# led_arrays.net
KiCad netlist of a schematic drawn in EAGLE
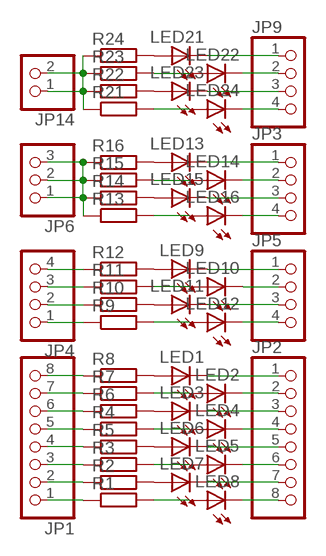
[diagram p0: schematic, sheet 1]

(export (version "E")
  (design (tool "Eeschema 10.0.6"))
  (components
    (comp (ref "JP1")
      (value "PINHD-1X8")
      (footprint "eagle-import:1X08")
      (libsource (lib "eagle-import") (part "PINHD-1X8"))
    )
    (comp (ref "JP2")
      (value "PINHD-1X8")
      (footprint "eagle-import:1X08")
      (libsource (lib "eagle-import") (part "PINHD-1X8"))
    )
    (comp (ref "JP3")
      (value "PINHD-1X4")
      (footprint "eagle-import:1X04")
      (libsource (lib "eagle-import") (part "PINHD-1X4"))
    )
    (comp (ref "JP4")
      (value "PINHD-1X4")
      (footprint "eagle-import:1X04")
      (libsource (lib "eagle-import") (part "PINHD-1X4"))
    )
    (comp (ref "JP5")
      (value "PINHD-1X4")
      (footprint "eagle-import:1X04")
      (libsource (lib "eagle-import") (part "PINHD-1X4"))
    )
    (comp (ref "JP6")
      (value "PINHD-1X3")
      (footprint "eagle-import:1X03")
      (libsource (lib "eagle-import") (part "PINHD-1X3"))
    )
    (comp (ref "JP9")
      (value "PINHD-1X4")
      (footprint "eagle-import:1X04")
      (libsource (lib "eagle-import") (part "PINHD-1X4"))
    )
    (comp (ref "JP14")
      (value "PINHD-1X2")
      (footprint "eagle-import:1X02")
      (libsource (lib "eagle-import") (part "PINHD-1X2"))
    )
    (comp (ref "LED1")
      (value "LEDSML0805")
      (footprint "eagle-import:SML0805")
      (libsource (lib "eagle-import") (part "LEDSML0805"))
    )
    (comp (ref "LED2")
      (value "LEDSML0805")
      (footprint "eagle-import:SML0805")
      (libsource (lib "eagle-import") (part "LEDSML0805"))
    )
    (comp (ref "LED3")
      (value "LEDSML0805")
      (footprint "eagle-import:SML0805")
      (libsource (lib "eagle-import") (part "LEDSML0805"))
    )
    (comp (ref "LED4")
      (value "LEDSML0805")
      (footprint "eagle-import:SML0805")
      (libsource (lib "eagle-import") (part "LEDSML0805"))
    )
    (comp (ref "LED5")
      (value "LEDSML0805")
      (footprint "eagle-import:SML0805")
      (libsource (lib "eagle-import") (part "LEDSML0805"))
    )
    (comp (ref "LED6")
      (value "LEDSML0805")
      (footprint "eagle-import:SML0805")
      (libsource (lib "eagle-import") (part "LEDSML0805"))
    )
    (comp (ref "LED7")
      (value "LEDSML0805")
      (footprint "eagle-import:SML0805")
      (libsource (lib "eagle-import") (part "LEDSML0805"))
    )
    (comp (ref "LED8")
      (value "LEDSML0805")
      (footprint "eagle-import:SML0805")
      (libsource (lib "eagle-import") (part "LEDSML0805"))
    )
    (comp (ref "LED9")
      (value "LEDSML0805")
      (footprint "eagle-import:SML0805")
      (libsource (lib "eagle-import") (part "LEDSML0805"))
    )
    (comp (ref "LED10")
      (value "LEDSML0805")
      (footprint "eagle-import:SML0805")
      (libsource (lib "eagle-import") (part "LEDSML0805"))
    )
    (comp (ref "LED11")
      (value "LEDSML0805")
      (footprint "eagle-import:SML0805")
      (libsource (lib "eagle-import") (part "LEDSML0805"))
    )
    (comp (ref "LED12")
      (value "LEDSML0805")
      (footprint "eagle-import:SML0805")
      (libsource (lib "eagle-import") (part "LEDSML0805"))
    )
    (comp (ref "LED13")
      (value "LEDSML0805")
      (footprint "eagle-import:SML0805")
      (libsource (lib "eagle-import") (part "LEDSML0805"))
    )
    (comp (ref "LED14")
      (value "LEDSML0805")
      (footprint "eagle-import:SML0805")
      (libsource (lib "eagle-import") (part "LEDSML0805"))
    )
    (comp (ref "LED15")
      (value "LEDSML0805")
      (footprint "eagle-import:SML0805")
      (libsource (lib "eagle-import") (part "LEDSML0805"))
    )
    (comp (ref "LED16")
      (value "LEDSML0805")
      (footprint "eagle-import:SML0805")
      (libsource (lib "eagle-import") (part "LEDSML0805"))
    )
    (comp (ref "LED21")
      (value "LEDSML0805")
      (footprint "eagle-import:SML0805")
      (libsource (lib "eagle-import") (part "LEDSML0805"))
    )
    (comp (ref "LED22")
      (value "LEDSML0805")
      (footprint "eagle-import:SML0805")
      (libsource (lib "eagle-import") (part "LEDSML0805"))
    )
    (comp (ref "LED23")
      (value "LEDSML0805")
      (footprint "eagle-import:SML0805")
      (libsource (lib "eagle-import") (part "LEDSML0805"))
    )
    (comp (ref "LED24")
      (value "LEDSML0805")
      (footprint "eagle-import:SML0805")
      (libsource (lib "eagle-import") (part "LEDSML0805"))
    )
    (comp (ref "R1")
      (value "R-EU_M0805")
      (footprint "eagle-import:M0805")
      (libsource (lib "eagle-import") (part "R-EU_M0805"))
    )
    (comp (ref "R2")
      (value "R-EU_M0805")
      (footprint "eagle-import:M0805")
      (libsource (lib "eagle-import") (part "R-EU_M0805"))
    )
    (comp (ref "R3")
      (value "R-EU_M0805")
      (footprint "eagle-import:M0805")
      (libsource (lib "eagle-import") (part "R-EU_M0805"))
    )
    (comp (ref "R4")
      (value "R-EU_M0805")
      (footprint "eagle-import:M0805")
      (libsource (lib "eagle-import") (part "R-EU_M0805"))
    )
    (comp (ref "R5")
      (value "R-EU_M0805")
      (footprint "eagle-import:M0805")
      (libsource (lib "eagle-import") (part "R-EU_M0805"))
    )
    (comp (ref "R6")
      (value "R-EU_M0805")
      (footprint "eagle-import:M0805")
      (libsource (lib "eagle-import") (part "R-EU_M0805"))
    )
    (comp (ref "R7")
      (value "R-EU_M0805")
      (footprint "eagle-import:M0805")
      (libsource (lib "eagle-import") (part "R-EU_M0805"))
    )
    (comp (ref "R8")
      (value "R-EU_M0805")
      (footprint "eagle-import:M0805")
      (libsource (lib "eagle-import") (part "R-EU_M0805"))
    )
    (comp (ref "R9")
      (value "R-EU_M0805")
      (footprint "eagle-import:M0805")
      (libsource (lib "eagle-import") (part "R-EU_M0805"))
    )
    (comp (ref "R10")
      (value "R-EU_M0805")
      (footprint "eagle-import:M0805")
      (libsource (lib "eagle-import") (part "R-EU_M0805"))
    )
    (comp (ref "R11")
      (value "R-EU_M0805")
      (footprint "eagle-import:M0805")
      (libsource (lib "eagle-import") (part "R-EU_M0805"))
    )
    (comp (ref "R12")
      (value "R-EU_M0805")
      (footprint "eagle-import:M0805")
      (libsource (lib "eagle-import") (part "R-EU_M0805"))
    )
    (comp (ref "R13")
      (value "R-EU_M0805")
      (footprint "eagle-import:M0805")
      (libsource (lib "eagle-import") (part "R-EU_M0805"))
    )
    (comp (ref "R14")
      (value "R-EU_M0805")
      (footprint "eagle-import:M0805")
      (libsource (lib "eagle-import") (part "R-EU_M0805"))
    )
    (comp (ref "R15")
      (value "R-EU_M0805")
      (footprint "eagle-import:M0805")
      (libsource (lib "eagle-import") (part "R-EU_M0805"))
    )
    (comp (ref "R16")
      (value "R-EU_M0805")
      (footprint "eagle-import:M0805")
      (libsource (lib "eagle-import") (part "R-EU_M0805"))
    )
    (comp (ref "R21")
      (value "R-EU_M0805")
      (footprint "eagle-import:M0805")
      (libsource (lib "eagle-import") (part "R-EU_M0805"))
    )
    (comp (ref "R22")
      (value "R-EU_M0805")
      (footprint "eagle-import:M0805")
      (libsource (lib "eagle-import") (part "R-EU_M0805"))
    )
    (comp (ref "R23")
      (value "R-EU_M0805")
      (footprint "eagle-import:M0805")
      (libsource (lib "eagle-import") (part "R-EU_M0805"))
    )
    (comp (ref "R24")
      (value "R-EU_M0805")
      (footprint "eagle-import:M0805")
      (libsource (lib "eagle-import") (part "R-EU_M0805"))
    )
  )
  (nets
    (net (code "1") (name "Net-(JP1-Pad1)") (class "Default")
      (node (ref "JP1") (pin "1") (pinfunction "1_1") (pintype "passive"))
      (node (ref "R1") (pin "1") (pinfunction "1_1") (pintype "passive"))
    )
    (net (code "2") (name "Net-(JP1-Pad2)") (class "Default")
      (node (ref "JP1") (pin "2") (pinfunction "2_2") (pintype "passive"))
      (node (ref "R2") (pin "1") (pinfunction "1_1") (pintype "passive"))
    )
    (net (code "3") (name "Net-(JP1-Pad3)") (class "Default")
      (node (ref "JP1") (pin "3") (pinfunction "3_3") (pintype "passive"))
      (node (ref "R3") (pin "1") (pinfunction "1_1") (pintype "passive"))
    )
    (net (code "4") (name "Net-(JP1-Pad4)") (class "Default")
      (node (ref "JP1") (pin "4") (pinfunction "4_4") (pintype "passive"))
      (node (ref "R5") (pin "1") (pinfunction "1_1") (pintype "passive"))
    )
    (net (code "5") (name "Net-(JP1-Pad5)") (class "Default")
      (node (ref "JP1") (pin "5") (pinfunction "5_5") (pintype "passive"))
      (node (ref "R4") (pin "1") (pinfunction "1_1") (pintype "passive"))
    )
    (net (code "6") (name "Net-(JP1-Pad6)") (class "Default")
      (node (ref "JP1") (pin "6") (pinfunction "6_6") (pintype "passive"))
      (node (ref "R6") (pin "1") (pinfunction "1_1") (pintype "passive"))
    )
    (net (code "7") (name "Net-(JP1-Pad7)") (class "Default")
      (node (ref "JP1") (pin "7") (pinfunction "7_7") (pintype "passive"))
      (node (ref "R7") (pin "1") (pinfunction "1_1") (pintype "passive"))
    )
    (net (code "8") (name "Net-(JP1-Pad8)") (class "Default")
      (node (ref "JP1") (pin "8") (pinfunction "8_8") (pintype "passive"))
      (node (ref "R8") (pin "1") (pinfunction "1_1") (pintype "passive"))
    )
    (net (code "9") (name "Net-(JP2-Pad1)") (class "Default")
      (node (ref "JP2") (pin "1") (pinfunction "1_1") (pintype "passive"))
      (node (ref "LED1") (pin "C") (pinfunction "C_C") (pintype "passive"))
    )
    (net (code "10") (name "Net-(JP2-Pad2)") (class "Default")
      (node (ref "JP2") (pin "2") (pinfunction "2_2") (pintype "passive"))
      (node (ref "LED2") (pin "C") (pinfunction "C_C") (pintype "passive"))
    )
    (net (code "11") (name "Net-(JP2-Pad3)") (class "Default")
      (node (ref "JP2") (pin "3") (pinfunction "3_3") (pintype "passive"))
      (node (ref "LED3") (pin "C") (pinfunction "C_C") (pintype "passive"))
    )
    (net (code "12") (name "Net-(JP2-Pad4)") (class "Default")
      (node (ref "JP2") (pin "4") (pinfunction "4_4") (pintype "passive"))
      (node (ref "LED4") (pin "C") (pinfunction "C_C") (pintype "passive"))
    )
    (net (code "13") (name "Net-(JP2-Pad5)") (class "Default")
      (node (ref "JP2") (pin "5") (pinfunction "5_5") (pintype "passive"))
      (node (ref "LED6") (pin "C") (pinfunction "C_C") (pintype "passive"))
    )
    (net (code "14") (name "Net-(JP2-Pad6)") (class "Default")
      (node (ref "JP2") (pin "6") (pinfunction "6_6") (pintype "passive"))
      (node (ref "LED5") (pin "C") (pinfunction "C_C") (pintype "passive"))
    )
    (net (code "15") (name "Net-(JP2-Pad7)") (class "Default")
      (node (ref "JP2") (pin "7") (pinfunction "7_7") (pintype "passive"))
      (node (ref "LED7") (pin "C") (pinfunction "C_C") (pintype "passive"))
    )
    (net (code "16") (name "Net-(JP2-Pad8)") (class "Default")
      (node (ref "JP2") (pin "8") (pinfunction "8_8") (pintype "passive"))
      (node (ref "LED8") (pin "C") (pinfunction "C_C") (pintype "passive"))
    )
    (net (code "17") (name "Net-(JP3-Pad1)") (class "Default")
      (node (ref "JP3") (pin "1") (pinfunction "1_1") (pintype "passive"))
      (node (ref "LED13") (pin "C") (pinfunction "C_C") (pintype "passive"))
    )
    (net (code "18") (name "Net-(JP3-Pad2)") (class "Default")
      (node (ref "JP3") (pin "2") (pinfunction "2_2") (pintype "passive"))
      (node (ref "LED14") (pin "C") (pinfunction "C_C") (pintype "passive"))
    )
    (net (code "19") (name "Net-(JP3-Pad3)") (class "Default")
      (node (ref "JP3") (pin "3") (pinfunction "3_3") (pintype "passive"))
      (node (ref "LED15") (pin "C") (pinfunction "C_C") (pintype "passive"))
    )
    (net (code "20") (name "Net-(JP3-Pad4)") (class "Default")
      (node (ref "JP3") (pin "4") (pinfunction "4_4") (pintype "passive"))
      (node (ref "LED16") (pin "C") (pinfunction "C_C") (pintype "passive"))
    )
    (net (code "21") (name "Net-(JP4-Pad1)") (class "Default")
      (node (ref "JP4") (pin "1") (pinfunction "1_1") (pintype "passive"))
      (node (ref "R9") (pin "1") (pinfunction "1_1") (pintype "passive"))
    )
    (net (code "22") (name "Net-(JP4-Pad2)") (class "Default")
      (node (ref "JP4") (pin "2") (pinfunction "2_2") (pintype "passive"))
      (node (ref "R10") (pin "1") (pinfunction "1_1") (pintype "passive"))
    )
    (net (code "23") (name "Net-(JP4-Pad3)") (class "Default")
      (node (ref "JP4") (pin "3") (pinfunction "3_3") (pintype "passive"))
      (node (ref "R11") (pin "1") (pinfunction "1_1") (pintype "passive"))
    )
    (net (code "24") (name "Net-(JP4-Pad4)") (class "Default")
      (node (ref "JP4") (pin "4") (pinfunction "4_4") (pintype "passive"))
      (node (ref "R12") (pin "1") (pinfunction "1_1") (pintype "passive"))
    )
    (net (code "25") (name "Net-(JP5-Pad1)") (class "Default")
      (node (ref "JP5") (pin "1") (pinfunction "1_1") (pintype "passive"))
      (node (ref "LED9") (pin "C") (pinfunction "C_C") (pintype "passive"))
    )
    (net (code "26") (name "Net-(JP5-Pad2)") (class "Default")
      (node (ref "JP5") (pin "2") (pinfunction "2_2") (pintype "passive"))
      (node (ref "LED10") (pin "C") (pinfunction "C_C") (pintype "passive"))
    )
    (net (code "27") (name "Net-(JP5-Pad3)") (class "Default")
      (node (ref "JP5") (pin "3") (pinfunction "3_3") (pintype "passive"))
      (node (ref "LED11") (pin "C") (pinfunction "C_C") (pintype "passive"))
    )
    (net (code "28") (name "Net-(JP5-Pad4)") (class "Default")
      (node (ref "JP5") (pin "4") (pinfunction "4_4") (pintype "passive"))
      (node (ref "LED12") (pin "C") (pinfunction "C_C") (pintype "passive"))
    )
    (net (code "29") (name "Net-(JP6-Pad1)") (class "Default")
      (node (ref "JP6") (pin "1") (pinfunction "1_1") (pintype "passive"))
      (node (ref "JP6") (pin "2") (pinfunction "2_2") (pintype "passive"))
      (node (ref "JP6") (pin "3") (pinfunction "3_3") (pintype "passive"))
      (node (ref "R13") (pin "1") (pinfunction "1_1") (pintype "passive"))
      (node (ref "R14") (pin "1") (pinfunction "1_1") (pintype "passive"))
      (node (ref "R15") (pin "1") (pinfunction "1_1") (pintype "passive"))
      (node (ref "R16") (pin "1") (pinfunction "1_1") (pintype "passive"))
    )
    (net (code "30") (name "Net-(JP9-Pad1)") (class "Default")
      (node (ref "JP9") (pin "1") (pinfunction "1_1") (pintype "passive"))
      (node (ref "LED21") (pin "C") (pinfunction "C_C") (pintype "passive"))
    )
    (net (code "31") (name "Net-(JP9-Pad2)") (class "Default")
      (node (ref "JP9") (pin "2") (pinfunction "2_2") (pintype "passive"))
      (node (ref "LED22") (pin "C") (pinfunction "C_C") (pintype "passive"))
    )
    (net (code "32") (name "Net-(JP9-Pad3)") (class "Default")
      (node (ref "JP9") (pin "3") (pinfunction "3_3") (pintype "passive"))
      (node (ref "LED23") (pin "C") (pinfunction "C_C") (pintype "passive"))
    )
    (net (code "33") (name "Net-(JP9-Pad4)") (class "Default")
      (node (ref "JP9") (pin "4") (pinfunction "4_4") (pintype "passive"))
      (node (ref "LED24") (pin "C") (pinfunction "C_C") (pintype "passive"))
    )
    (net (code "34") (name "Net-(JP14-Pad1)") (class "Default")
      (node (ref "JP14") (pin "1") (pinfunction "1_1") (pintype "passive"))
      (node (ref "JP14") (pin "2") (pinfunction "2_2") (pintype "passive"))
      (node (ref "R21") (pin "1") (pinfunction "1_1") (pintype "passive"))
      (node (ref "R22") (pin "1") (pinfunction "1_1") (pintype "passive"))
      (node (ref "R23") (pin "1") (pinfunction "1_1") (pintype "passive"))
      (node (ref "R24") (pin "1") (pinfunction "1_1") (pintype "passive"))
    )
    (net (code "35") (name "Net-(LED1-PadA)") (class "Default")
      (node (ref "LED1") (pin "A") (pinfunction "A_A") (pintype "passive"))
      (node (ref "R8") (pin "2") (pinfunction "2_2") (pintype "passive"))
    )
    (net (code "36") (name "Net-(LED2-PadA)") (class "Default")
      (node (ref "LED2") (pin "A") (pinfunction "A_A") (pintype "passive"))
      (node (ref "R7") (pin "2") (pinfunction "2_2") (pintype "passive"))
    )
    (net (code "37") (name "Net-(LED3-PadA)") (class "Default")
      (node (ref "LED3") (pin "A") (pinfunction "A_A") (pintype "passive"))
      (node (ref "R6") (pin "2") (pinfunction "2_2") (pintype "passive"))
    )
    (net (code "38") (name "Net-(LED4-PadA)") (class "Default")
      (node (ref "LED4") (pin "A") (pinfunction "A_A") (pintype "passive"))
      (node (ref "R4") (pin "2") (pinfunction "2_2") (pintype "passive"))
    )
    (net (code "39") (name "Net-(LED5-PadA)") (class "Default")
      (node (ref "LED5") (pin "A") (pinfunction "A_A") (pintype "passive"))
      (node (ref "R3") (pin "2") (pinfunction "2_2") (pintype "passive"))
    )
    (net (code "40") (name "Net-(LED6-PadA)") (class "Default")
      (node (ref "LED6") (pin "A") (pinfunction "A_A") (pintype "passive"))
      (node (ref "R5") (pin "2") (pinfunction "2_2") (pintype "passive"))
    )
    (net (code "41") (name "Net-(LED7-PadA)") (class "Default")
      (node (ref "LED7") (pin "A") (pinfunction "A_A") (pintype "passive"))
      (node (ref "R2") (pin "2") (pinfunction "2_2") (pintype "passive"))
    )
    (net (code "42") (name "Net-(LED8-PadA)") (class "Default")
      (node (ref "LED8") (pin "A") (pinfunction "A_A") (pintype "passive"))
      (node (ref "R1") (pin "2") (pinfunction "2_2") (pintype "passive"))
    )
    (net (code "43") (name "Net-(LED9-PadA)") (class "Default")
      (node (ref "LED9") (pin "A") (pinfunction "A_A") (pintype "passive"))
      (node (ref "R12") (pin "2") (pinfunction "2_2") (pintype "passive"))
    )
    (net (code "44") (name "Net-(LED10-PadA)") (class "Default")
      (node (ref "LED10") (pin "A") (pinfunction "A_A") (pintype "passive"))
      (node (ref "R11") (pin "2") (pinfunction "2_2") (pintype "passive"))
    )
    (net (code "45") (name "Net-(LED11-PadA)") (class "Default")
      (node (ref "LED11") (pin "A") (pinfunction "A_A") (pintype "passive"))
      (node (ref "R10") (pin "2") (pinfunction "2_2") (pintype "passive"))
    )
    (net (code "46") (name "Net-(LED12-PadA)") (class "Default")
      (node (ref "LED12") (pin "A") (pinfunction "A_A") (pintype "passive"))
      (node (ref "R9") (pin "2") (pinfunction "2_2") (pintype "passive"))
    )
    (net (code "47") (name "Net-(LED13-PadA)") (class "Default")
      (node (ref "LED13") (pin "A") (pinfunction "A_A") (pintype "passive"))
      (node (ref "R16") (pin "2") (pinfunction "2_2") (pintype "passive"))
    )
    (net (code "48") (name "Net-(LED14-PadA)") (class "Default")
      (node (ref "LED14") (pin "A") (pinfunction "A_A") (pintype "passive"))
      (node (ref "R15") (pin "2") (pinfunction "2_2") (pintype "passive"))
    )
    (net (code "49") (name "Net-(LED15-PadA)") (class "Default")
      (node (ref "LED15") (pin "A") (pinfunction "A_A") (pintype "passive"))
      (node (ref "R14") (pin "2") (pinfunction "2_2") (pintype "passive"))
    )
    (net (code "50") (name "Net-(LED16-PadA)") (class "Default")
      (node (ref "LED16") (pin "A") (pinfunction "A_A") (pintype "passive"))
      (node (ref "R13") (pin "2") (pinfunction "2_2") (pintype "passive"))
    )
    (net (code "51") (name "Net-(LED21-PadA)") (class "Default")
      (node (ref "LED21") (pin "A") (pinfunction "A_A") (pintype "passive"))
      (node (ref "R24") (pin "2") (pinfunction "2_2") (pintype "passive"))
    )
    (net (code "52") (name "Net-(LED22-PadA)") (class "Default")
      (node (ref "LED22") (pin "A") (pinfunction "A_A") (pintype "passive"))
      (node (ref "R23") (pin "2") (pinfunction "2_2") (pintype "passive"))
    )
    (net (code "53") (name "Net-(LED23-PadA)") (class "Default")
      (node (ref "LED23") (pin "A") (pinfunction "A_A") (pintype "passive"))
      (node (ref "R22") (pin "2") (pinfunction "2_2") (pintype "passive"))
    )
    (net (code "54") (name "Net-(LED24-PadA)") (class "Default")
      (node (ref "LED24") (pin "A") (pinfunction "A_A") (pintype "passive"))
      (node (ref "R21") (pin "2") (pinfunction "2_2") (pintype "passive"))
    )
  )
)
